# AC_dimmer_HLK.net
KiCad netlist of a schematic drawn in EAGLE
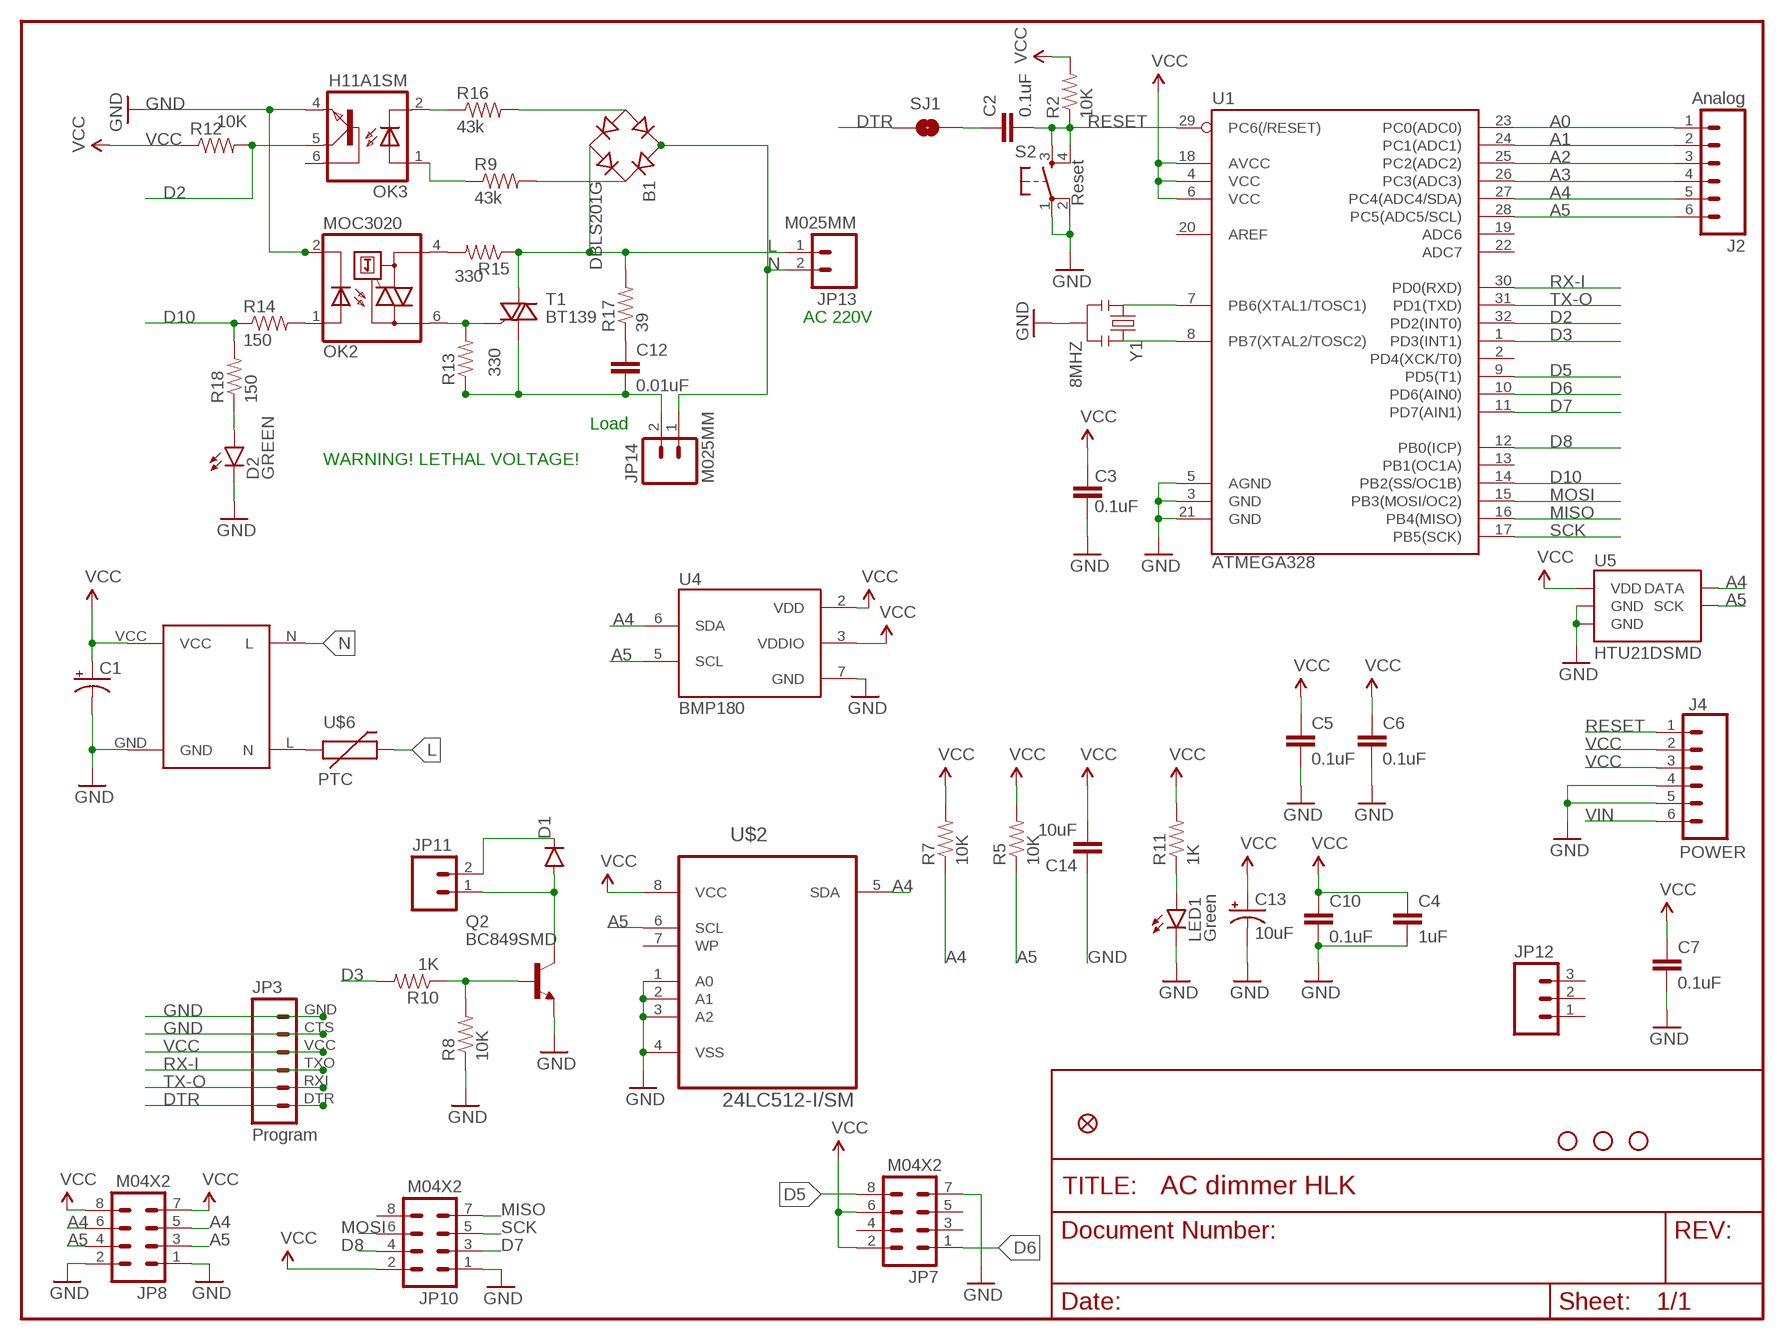
[diagram p0: schematic, sheet 1]

(export (version "E")
  (design (tool "Eeschema 10.0.6"))
  (components
    (comp (ref "B1")
      (value "DBLS201G")
      (footprint "eagle-import:DBS")
      (libsource (lib "eagle-import") (part "DB?GLS201"))
    )
    (comp (ref "C1")
      (value "CAP_POL3528-KIT")
      (footprint "eagle-import:EIA3528-KIT")
      (libsource (lib "eagle-import") (part "CAP_POL3528-KIT"))
    )
    (comp (ref "C2")
      (value "0.1uF")
      (footprint "eagle-import:0805")
      (libsource (lib "eagle-import") (part "CAP0805"))
    )
    (comp (ref "C3")
      (value "0.1uF")
      (footprint "eagle-import:0805")
      (libsource (lib "eagle-import") (part "CAP0805"))
    )
    (comp (ref "C4")
      (value "1uF")
      (footprint "eagle-import:0805")
      (libsource (lib "eagle-import") (part "CAP0805"))
    )
    (comp (ref "C5")
      (value "0.1uF")
      (footprint "eagle-import:0805")
      (libsource (lib "eagle-import") (part "CAP0805"))
    )
    (comp (ref "C6")
      (value "0.1uF")
      (footprint "eagle-import:0805")
      (libsource (lib "eagle-import") (part "CAP0805"))
    )
    (comp (ref "C7")
      (value "0.1uF")
      (footprint "eagle-import:0805")
      (libsource (lib "eagle-import") (part "CAP0805"))
    )
    (comp (ref "C10")
      (value "0.1uF")
      (footprint "eagle-import:0805")
      (libsource (lib "eagle-import") (part "CAP0805"))
    )
    (comp (ref "C12")
      (value "0.01uF")
      (footprint "eagle-import:C1206")
      (libsource (lib "eagle-import") (part "C-EUC1206"))
    )
    (comp (ref "C13")
      (value "10uF")
      (footprint "eagle-import:EIA3216")
      (libsource (lib "eagle-import") (part "CAP_POL1206"))
    )
    (comp (ref "C14")
      (value "10uF")
      (footprint "eagle-import:1206")
      (libsource (lib "eagle-import") (part "SparkFun-Capacitors_CAP1206"))
    )
    (comp (ref "D1")
      (value "DIODESOD")
      (footprint "eagle-import:SOD-323")
      (libsource (lib "eagle-import") (part "DIODESOD"))
    )
    (comp (ref "D2")
      (value "GREEN")
      (footprint "eagle-import:LED-0603")
      (libsource (lib "eagle-import") (part "LED0603"))
    )
    (comp (ref "J2")
      (value "Analog")
      (footprint "eagle-import:1X06")
      (libsource (lib "eagle-import") (part "M06SIP"))
    )
    (comp (ref "J4")
      (value "POWER")
      (footprint "eagle-import:1X06")
      (libsource (lib "eagle-import") (part "M06SIP"))
    )
    (comp (ref "JP2")
      (value "FIDUCIAL1X2.5")
      (footprint "eagle-import:FIDUCIAL-1X2.5")
      (libsource (lib "eagle-import") (part "FIDUCIAL1X2.5"))
    )
    (comp (ref "JP3")
      (value "Program")
      (footprint "eagle-import:1X06")
      (libsource (lib "eagle-import") (part "SparkFun-Connectors_M06SIP"))
    )
    (comp (ref "JP7")
      (value "M04X2")
      (footprint "eagle-import:2X4")
      (libsource (lib "eagle-import") (part "M04X2"))
    )
    (comp (ref "JP8")
      (value "M04X2")
      (footprint "eagle-import:2X4")
      (libsource (lib "eagle-import") (part "M04X2"))
    )
    (comp (ref "JP10")
      (value "M04X2")
      (footprint "eagle-import:2X4")
      (libsource (lib "eagle-import") (part "M04X2"))
    )
    (comp (ref "JP11")
      (value "M02PTH")
      (footprint "eagle-import:1X02")
      (libsource (lib "eagle-import") (part "M02PTH"))
    )
    (comp (ref "JP12")
      (value "M03PTH")
      (footprint "eagle-import:1X03")
      (libsource (lib "eagle-import") (part "M03PTH"))
    )
    (comp (ref "JP13")
      (value "M025MM")
      (footprint "eagle-import:SCREWTERMINAL-5MM-2")
      (libsource (lib "eagle-import") (part "M025MM"))
    )
    (comp (ref "JP14")
      (value "M025MM")
      (footprint "eagle-import:SCREWTERMINAL-5MM-2")
      (libsource (lib "eagle-import") (part "M025MM"))
    )
    (comp (ref "LED1")
      (value "Green")
      (footprint "eagle-import:LED-0603")
      (libsource (lib "eagle-import") (part "LED0603"))
    )
    (comp (ref "OK2")
      (value "MOC3020")
      (footprint "eagle-import:DIL6-SMD")
      (fields (field (name "MF") "FAIRCHILD SEMICONDUCTOR") (field (name "MPN") "MOC3031SM"))
      (libsource (lib "eagle-import") (part "MOC30S31"))
    )
    (comp (ref "OK3")
      (value "H11A1SM")
      (footprint "eagle-import:DIL6-SMD")
      (libsource (lib "eagle-import") (part "H11A?MS1"))
    )
    (comp (ref "Q2")
      (value "BC849SMD")
      (footprint "eagle-import:SOT23-BEC")
      (libsource (lib "eagle-import") (part "BC849SMD"))
    )
    (comp (ref "R2")
      (value "10K")
      (footprint "eagle-import:0805")
      (libsource (lib "eagle-import") (part "RESISTOR0805-RES"))
    )
    (comp (ref "R5")
      (value "10K")
      (footprint "eagle-import:0805")
      (libsource (lib "eagle-import") (part "RESISTOR0805-RES"))
    )
    (comp (ref "R7")
      (value "10K")
      (footprint "eagle-import:0805")
      (libsource (lib "eagle-import") (part "RESISTOR0805-RES"))
    )
    (comp (ref "R8")
      (value "10K")
      (footprint "eagle-import:0805")
      (libsource (lib "eagle-import") (part "RESISTOR0805-RES"))
    )
    (comp (ref "R9")
      (value "43k")
      (footprint "eagle-import:1206")
      (fields (field (name "K") "45K"))
      (libsource (lib "eagle-import") (part "SparkFun-Resistors_RESISTOR1206"))
    )
    (comp (ref "R10")
      (value "1K")
      (footprint "eagle-import:0805")
      (libsource (lib "eagle-import") (part "RESISTOR0805-RES"))
    )
    (comp (ref "R11")
      (value "1K")
      (footprint "eagle-import:0805")
      (libsource (lib "eagle-import") (part "RESISTOR0805-RES"))
    )
    (comp (ref "R12")
      (value "RESISTOR0805-RES")
      (footprint "eagle-import:0805")
      (fields (field (name "OHM") "10K"))
      (libsource (lib "eagle-import") (part "SparkFun-Resistors_RESISTOR0805-RES"))
    )
    (comp (ref "R13")
      (value "RESISTOR1206")
      (footprint "eagle-import:1206")
      (fields (field (name "OHM") "330"))
      (libsource (lib "eagle-import") (part "SparkFun-Resistors_RESISTOR1206"))
    )
    (comp (ref "R14")
      (value "150")
      (footprint "eagle-import:0805")
      (fields (field (name "OHM") "330"))
      (libsource (lib "eagle-import") (part "SparkFun-Resistors_RESISTOR0805-RES"))
    )
    (comp (ref "R15")
      (value "RESISTOR1206")
      (footprint "eagle-import:1206")
      (fields (field (name "OHM") "330"))
      (libsource (lib "eagle-import") (part "SparkFun-Resistors_RESISTOR1206"))
    )
    (comp (ref "R16")
      (value "43k")
      (footprint "eagle-import:1206")
      (fields (field (name "K") "45K"))
      (libsource (lib "eagle-import") (part "SparkFun-Resistors_RESISTOR1206"))
    )
    (comp (ref "R17")
      (value "39")
      (footprint "eagle-import:1206")
      (fields (field (name "K") "45K"))
      (libsource (lib "eagle-import") (part "SparkFun-Resistors_RESISTOR1206"))
    )
    (comp (ref "R18")
      (value "150")
      (footprint "eagle-import:0805")
      (fields (field (name "OHM") "330"))
      (libsource (lib "eagle-import") (part "SparkFun-Resistors_RESISTOR0805-RES"))
    )
    (comp (ref "S2")
      (value "Reset")
      (footprint "eagle-import:TACTILE_SWITCH_SMD")
      (libsource (lib "eagle-import") (part "TAC_SWITCHSMD"))
    )
    (comp (ref "SJ1")
      (value "SOLDERJUMPERNC2")
      (footprint "eagle-import:SJ_2S-NOTRACE")
      (libsource (lib "eagle-import") (part "SOLDERJUMPERNC2"))
    )
    (comp (ref "T1")
      (value "BT139")
      (footprint "eagle-import:TO220AB")
      (libsource (lib "eagle-import") (part "BT136"))
    )
    (comp (ref "U$2")
      (value "24LC512-I/SM")
      (footprint "eagle-import:SOIC127P794X203-8N")
      (libsource (lib "eagle-import") (part "24LC512-I/SM"))
    )
    (comp (ref "U$3")
      (value "STAND-OFFTIGHT")
      (footprint "eagle-import:STAND-OFF-TIGHT")
      (libsource (lib "eagle-import") (part "STAND-OFFTIGHT"))
    )
    (comp (ref "U$5")
      (value "AC-DCHLK01")
      (footprint "eagle-import:HLK-PM01")
      (libsource (lib "eagle-import") (part "AC-DCHLK01"))
    )
    (comp (ref "U$6")
      (value "PTC")
      (footprint "eagle-import:MC331XX")
      (libsource (lib "eagle-import") (part "PTC"))
    )
    (comp (ref "U$9")
      (value "STAND-OFFTIGHT")
      (footprint "eagle-import:STAND-OFF-TIGHT")
      (libsource (lib "eagle-import") (part "STAND-OFFTIGHT"))
    )
    (comp (ref "U$10")
      (value "STAND-OFFTIGHT")
      (footprint "eagle-import:STAND-OFF-TIGHT")
      (libsource (lib "eagle-import") (part "STAND-OFFTIGHT"))
    )
    (comp (ref "U1")
      (value "ATMEGA328")
      (footprint "eagle-import:TQFP32-08")
      (libsource (lib "eagle-import") (part "ATMEGA168"))
    )
    (comp (ref "U4")
      (value "BMP180")
      (footprint "eagle-import:BMP180")
      (libsource (lib "eagle-import") (part "BMP180"))
    )
    (comp (ref "U5")
      (value "HTU21DSMD")
      (footprint "eagle-import:HTU21D")
      (libsource (lib "eagle-import") (part "HTU21DSMD"))
    )
    (comp (ref "Y1")
      (value "8MHZ")
      (footprint "eagle-import:RESONATOR-SMD")
      (libsource (lib "eagle-import") (part "RESONATOR8MHZ"))
    )
  )
  (nets
    (net (code "1") (name "/A0") (class "Default")
      (node (ref "J2") (pin "1") (pinfunction "1_1") (pintype "passive"))
      (node (ref "U1") (pin "23") (pinfunction "PC0(ADC0)_23") (pintype "bidirectional"))
    )
    (net (code "2") (name "/A1") (class "Default")
      (node (ref "J2") (pin "2") (pinfunction "2_2") (pintype "passive"))
      (node (ref "U1") (pin "24") (pinfunction "PC1(ADC1)_24") (pintype "bidirectional"))
    )
    (net (code "3") (name "/A2") (class "Default")
      (node (ref "J2") (pin "3") (pinfunction "3_3") (pintype "passive"))
      (node (ref "U1") (pin "25") (pinfunction "PC2(ADC2)_25") (pintype "bidirectional"))
    )
    (net (code "4") (name "/A3") (class "Default")
      (node (ref "J2") (pin "4") (pinfunction "4_4") (pintype "passive"))
      (node (ref "U1") (pin "26") (pinfunction "PC3(ADC3)_26") (pintype "bidirectional"))
    )
    (net (code "5") (name "/A4") (class "Default")
      (node (ref "J2") (pin "5") (pinfunction "5_5") (pintype "passive"))
      (node (ref "JP8") (pin "5") (pinfunction "5_5") (pintype "passive"))
      (node (ref "JP8") (pin "6") (pinfunction "6_6") (pintype "passive"))
      (node (ref "R7") (pin "1") (pinfunction "1_1") (pintype "passive"))
      (node (ref "U$2") (pin "5") (pinfunction "SDA_5") (pintype "bidirectional"))
      (node (ref "U1") (pin "27") (pinfunction "PC4(ADC4/SDA)_27") (pintype "bidirectional"))
      (node (ref "U4") (pin "6") (pinfunction "SDA_6") (pintype "bidirectional"))
      (node (ref "U5") (pin "DATA") (pinfunction "DATA_DATA") (pintype "bidirectional"))
    )
    (net (code "6") (name "/A5") (class "Default")
      (node (ref "J2") (pin "6") (pinfunction "6_6") (pintype "passive"))
      (node (ref "JP8") (pin "3") (pinfunction "3_3") (pintype "passive"))
      (node (ref "JP8") (pin "4") (pinfunction "4_4") (pintype "passive"))
      (node (ref "R5") (pin "1") (pinfunction "1_1") (pintype "passive"))
      (node (ref "U$2") (pin "6") (pinfunction "SCL_6") (pintype "input"))
      (node (ref "U1") (pin "28") (pinfunction "PC5(ADC5/SCL)_28") (pintype "bidirectional"))
      (node (ref "U4") (pin "5") (pinfunction "SCL_5") (pintype "input"))
      (node (ref "U5") (pin "SCK") (pinfunction "SCK_SCK") (pintype "input"))
    )
    (net (code "7") (name "/D2") (class "Default")
      (node (ref "OK3") (pin "5") (pinfunction "COL_5") (pintype "passive"))
      (node (ref "R12") (pin "2") (pinfunction "2_2") (pintype "passive"))
      (node (ref "U1") (pin "32") (pinfunction "PD2(INT0)_32") (pintype "bidirectional"))
    )
    (net (code "8") (name "/D3") (class "Default")
      (node (ref "R10") (pin "2") (pinfunction "2_2") (pintype "passive"))
      (node (ref "U1") (pin "1") (pinfunction "PD3(INT1)_1") (pintype "bidirectional"))
    )
    (net (code "9") (name "/D7") (class "Default")
      (node (ref "JP10") (pin "3") (pinfunction "3_3") (pintype "passive"))
      (node (ref "U1") (pin "11") (pinfunction "PD7(AIN1)_11") (pintype "bidirectional"))
    )
    (net (code "10") (name "/D8") (class "Default")
      (node (ref "JP10") (pin "4") (pinfunction "4_4") (pintype "passive"))
      (node (ref "U1") (pin "12") (pinfunction "PB0(ICP)_12") (pintype "bidirectional"))
    )
    (net (code "11") (name "/D10") (class "Default")
      (node (ref "R14") (pin "1") (pinfunction "1_1") (pintype "passive"))
      (node (ref "R18") (pin "2") (pinfunction "2_2") (pintype "passive"))
      (node (ref "U1") (pin "14") (pinfunction "PB2(SS/OC1B)_14") (pintype "bidirectional"))
    )
    (net (code "12") (name "/DTR") (class "Default")
      (node (ref "JP3") (pin "DTR") (pinfunction "1_DTR") (pintype "passive"))
      (node (ref "SJ1") (pin "1") (pinfunction "1_1") (pintype "passive"))
    )
    (net (code "13") (name "/MISO") (class "Default")
      (node (ref "JP10") (pin "7") (pinfunction "7_7") (pintype "passive"))
      (node (ref "U1") (pin "16") (pinfunction "PB4(MISO)_16") (pintype "bidirectional"))
    )
    (net (code "14") (name "/MOSI") (class "Default")
      (node (ref "JP10") (pin "6") (pinfunction "6_6") (pintype "passive"))
      (node (ref "U1") (pin "15") (pinfunction "PB3(MOSI/OC2)_15") (pintype "bidirectional"))
    )
    (net (code "15") (name "/RESET") (class "Default")
      (node (ref "C2") (pin "2") (pinfunction "2_2") (pintype "passive"))
      (node (ref "J4") (pin "1") (pinfunction "1_1") (pintype "passive"))
      (node (ref "R2") (pin "1") (pinfunction "1_1") (pintype "passive"))
      (node (ref "S2") (pin "3") (pinfunction "3_3") (pintype "passive"))
      (node (ref "S2") (pin "4") (pinfunction "4_4") (pintype "passive"))
      (node (ref "U1") (pin "29") (pinfunction "PC6(/RESET)_29") (pintype "bidirectional"))
    )
    (net (code "16") (name "/RX-I") (class "Default")
      (node (ref "JP3") (pin "TXO") (pinfunction "3_TXO") (pintype "passive"))
      (node (ref "U1") (pin "30") (pinfunction "PD0(RXD)_30") (pintype "bidirectional"))
    )
    (net (code "17") (name "/SCK") (class "Default")
      (node (ref "JP10") (pin "5") (pinfunction "5_5") (pintype "passive"))
      (node (ref "U1") (pin "17") (pinfunction "PB5(SCK)_17") (pintype "bidirectional"))
    )
    (net (code "18") (name "/TX-O") (class "Default")
      (node (ref "JP3") (pin "RXI") (pinfunction "2_RXI") (pintype "passive"))
      (node (ref "U1") (pin "31") (pinfunction "PD1(TXD)_31") (pintype "bidirectional"))
    )
    (net (code "19") (name "/VIN") (class "Default")
      (node (ref "J4") (pin "6") (pinfunction "6_6") (pintype "passive"))
    )
    (net (code "20") (name "D5") (class "Default")
      (node (ref "JP7") (pin "8") (pinfunction "8_8") (pintype "passive"))
      (node (ref "U1") (pin "9") (pinfunction "PD5(T1)_9") (pintype "bidirectional"))
    )
    (net (code "21") (name "D6") (class "Default")
      (node (ref "JP7") (pin "1") (pinfunction "1_1") (pintype "passive"))
      (node (ref "U1") (pin "10") (pinfunction "PD6(AIN0)_10") (pintype "bidirectional"))
    )
    (net (code "22") (name "GND") (class "Default")
      (node (ref "C1") (pin "C") (pinfunction "-_C") (pintype "passive"))
      (node (ref "C10") (pin "2") (pinfunction "2_2") (pintype "passive"))
      (node (ref "C13") (pin "C") (pinfunction "-_C") (pintype "passive"))
      (node (ref "C14") (pin "1") (pinfunction "1_1") (pintype "passive"))
      (node (ref "C3") (pin "1") (pinfunction "1_1") (pintype "passive"))
      (node (ref "C4") (pin "2") (pinfunction "2_2") (pintype "passive"))
      (node (ref "C5") (pin "2") (pinfunction "2_2") (pintype "passive"))
      (node (ref "C6") (pin "2") (pinfunction "2_2") (pintype "passive"))
      (node (ref "C7") (pin "2") (pinfunction "2_2") (pintype "passive"))
      (node (ref "D2") (pin "C") (pinfunction "C_C") (pintype "passive"))
      (node (ref "J4") (pin "4") (pinfunction "4_4") (pintype "passive"))
      (node (ref "J4") (pin "5") (pinfunction "5_5") (pintype "passive"))
      (node (ref "JP10") (pin "1") (pinfunction "1_1") (pintype "passive"))
      (node (ref "JP3") (pin "CTS") (pinfunction "5_CTS") (pintype "passive"))
      (node (ref "JP3") (pin "GND") (pinfunction "6_GND") (pintype "passive"))
      (node (ref "JP7") (pin "7") (pinfunction "7_7") (pintype "passive"))
      (node (ref "JP8") (pin "1") (pinfunction "1_1") (pintype "passive"))
      (node (ref "JP8") (pin "2") (pinfunction "2_2") (pintype "passive"))
      (node (ref "LED1") (pin "C") (pinfunction "C_C") (pintype "passive"))
      (node (ref "OK2") (pin "2") (pinfunction "C_2") (pintype "passive"))
      (node (ref "OK3") (pin "4") (pinfunction "EMI_4") (pintype "passive"))
      (node (ref "Q2") (pin "E") (pinfunction "E_E") (pintype "passive"))
      (node (ref "R8") (pin "1") (pinfunction "1_1") (pintype "passive"))
      (node (ref "S2") (pin "1") (pinfunction "1_1") (pintype "passive"))
      (node (ref "S2") (pin "2") (pinfunction "2_2") (pintype "passive"))
      (node (ref "U$2") (pin "1") (pinfunction "A0_1") (pintype "input"))
      (node (ref "U$2") (pin "2") (pinfunction "A1_2") (pintype "input"))
      (node (ref "U$2") (pin "3") (pinfunction "A2_3") (pintype "input"))
      (node (ref "U$2") (pin "4") (pinfunction "VSS_4") (pintype "passive"))
      (node (ref "U$5") (pin "GND") (pinfunction "GND_GND") (pintype "bidirectional"))
      (node (ref "U1") (pin "21") (pinfunction "GND_21") (pintype "bidirectional"))
      (node (ref "U1") (pin "3") (pinfunction "GND_3") (pintype "bidirectional"))
      (node (ref "U1") (pin "5") (pinfunction "AGND_5") (pintype "bidirectional"))
      (node (ref "U4") (pin "7") (pinfunction "GND_7") (pintype "power_in"))
      (node (ref "U5") (pin "7") (pinfunction "GND_7") (pintype "power_in"))
      (node (ref "U5") (pin "GND") (pinfunction "GND_GND") (pintype "power_in"))
      (node (ref "Y1") (pin "2") (pinfunction "2_2") (pintype "passive"))
    )
    (net (code "23") (name "L") (class "Default")
      (node (ref "B1") (pin "AC2") (pinfunction "AC2_AC2") (pintype "passive"))
      (node (ref "JP13") (pin "1") (pinfunction "1_1") (pintype "passive"))
      (node (ref "R15") (pin "1") (pinfunction "1_1") (pintype "passive"))
      (node (ref "R17") (pin "2") (pinfunction "2_2") (pintype "passive"))
      (node (ref "T1") (pin "2") (pinfunction "A2_2") (pintype "passive"))
      (node (ref "U$6") (pin "P$2") (pinfunction "2_P$2") (pintype "bidirectional"))
    )
    (net (code "24") (name "N") (class "Default")
      (node (ref "B1") (pin "AC1") (pinfunction "AC1_AC1") (pintype "passive"))
      (node (ref "JP13") (pin "2") (pinfunction "2_2") (pintype "passive"))
      (node (ref "JP14") (pin "1") (pinfunction "1_1") (pintype "passive"))
      (node (ref "U$5") (pin "N") (pinfunction "L_N") (pintype "bidirectional"))
    )
    (net (code "25") (name "Net-(B1-Pad+)") (class "Default")
      (node (ref "B1") (pin "+") (pinfunction "+_+") (pintype "passive"))
      (node (ref "R9") (pin "2") (pinfunction "2_2") (pintype "passive"))
    )
    (net (code "26") (name "Net-(B1-Pad-)") (class "Default")
      (node (ref "B1") (pin "-") (pinfunction "-_-") (pintype "passive"))
      (node (ref "R16") (pin "2") (pinfunction "2_2") (pintype "passive"))
    )
    (net (code "27") (name "Net-(C2-Pad1)") (class "Default")
      (node (ref "C2") (pin "1") (pinfunction "1_1") (pintype "passive"))
      (node (ref "SJ1") (pin "2") (pinfunction "2_2") (pintype "passive"))
    )
    (net (code "28") (name "Net-(C12-Pad1)") (class "Default")
      (node (ref "C12") (pin "1") (pinfunction "1_1") (pintype "passive"))
      (node (ref "R17") (pin "1") (pinfunction "1_1") (pintype "passive"))
    )
    (net (code "29") (name "Net-(D1-PadA)") (class "Default")
      (node (ref "D1") (pin "A") (pinfunction "A_A") (pintype "passive"))
      (node (ref "JP11") (pin "1") (pinfunction "1_1") (pintype "passive"))
      (node (ref "Q2") (pin "C") (pinfunction "C_C") (pintype "passive"))
    )
    (net (code "30") (name "Net-(D1-PadC)") (class "Default")
      (node (ref "D1") (pin "C") (pinfunction "C_C") (pintype "passive"))
      (node (ref "JP11") (pin "2") (pinfunction "2_2") (pintype "passive"))
    )
    (net (code "31") (name "Net-(D2-PadA)") (class "Default")
      (node (ref "D2") (pin "A") (pinfunction "A_A") (pintype "passive"))
      (node (ref "R18") (pin "1") (pinfunction "1_1") (pintype "passive"))
    )
    (net (code "32") (name "Net-(LED1-PadA)") (class "Default")
      (node (ref "LED1") (pin "A") (pinfunction "A_A") (pintype "passive"))
      (node (ref "R11") (pin "1") (pinfunction "1_1") (pintype "passive"))
    )
    (net (code "33") (name "Net-(OK2-A)") (class "Default")
      (node (ref "OK2") (pin "1") (pinfunction "A_1") (pintype "passive"))
      (node (ref "R14") (pin "2") (pinfunction "2_2") (pintype "passive"))
    )
    (net (code "34") (name "Net-(OK2-A1)") (class "Default")
      (node (ref "OK2") (pin "4") (pinfunction "A1_4") (pintype "passive"))
      (node (ref "R15") (pin "2") (pinfunction "2_2") (pintype "passive"))
    )
    (net (code "35") (name "Net-(OK2-A2)") (class "Default")
      (node (ref "OK2") (pin "6") (pinfunction "A2_6") (pintype "passive"))
      (node (ref "R13") (pin "2") (pinfunction "2_2") (pintype "passive"))
      (node (ref "T1") (pin "3") (pinfunction "G_3") (pintype "passive"))
    )
    (net (code "36") (name "Net-(OK3-A)") (class "Default")
      (node (ref "OK3") (pin "1") (pinfunction "A_1") (pintype "passive"))
      (node (ref "R9") (pin "1") (pinfunction "1_1") (pintype "passive"))
    )
    (net (code "37") (name "Net-(OK3-C)") (class "Default")
      (node (ref "OK3") (pin "2") (pinfunction "C_2") (pintype "passive"))
      (node (ref "R16") (pin "1") (pinfunction "1_1") (pintype "passive"))
    )
    (net (code "38") (name "Net-(Q2-PadB)") (class "Default")
      (node (ref "Q2") (pin "B") (pinfunction "B_B") (pintype "passive"))
      (node (ref "R10") (pin "1") (pinfunction "1_1") (pintype "passive"))
      (node (ref "R8") (pin "2") (pinfunction "2_2") (pintype "passive"))
    )
    (net (code "39") (name "Net-(T1-A1)") (class "Default")
      (node (ref "C12") (pin "2") (pinfunction "2_2") (pintype "passive"))
      (node (ref "JP14") (pin "2") (pinfunction "2_2") (pintype "passive"))
      (node (ref "R13") (pin "1") (pinfunction "1_1") (pintype "passive"))
      (node (ref "T1") (pin "1") (pinfunction "A1_1") (pintype "passive"))
    )
    (net (code "40") (name "Net-(U$5-N)") (class "Default")
      (node (ref "U$5") (pin "L") (pinfunction "N_L") (pintype "bidirectional"))
      (node (ref "U$6") (pin "P$1") (pinfunction "1_P$1") (pintype "bidirectional"))
    )
    (net (code "41") (name "Net-(U1-PB6(XTAL1{slash}TOSC1))") (class "Default")
      (node (ref "U1") (pin "7") (pinfunction "PB6(XTAL1/TOSC1)_7") (pintype "bidirectional"))
      (node (ref "Y1") (pin "1") (pinfunction "1_1") (pintype "passive"))
    )
    (net (code "42") (name "Net-(U1-PB7(XTAL2{slash}TOSC2))") (class "Default")
      (node (ref "U1") (pin "8") (pinfunction "PB7(XTAL2/TOSC2)_8") (pintype "bidirectional"))
      (node (ref "Y1") (pin "3") (pinfunction "3_3") (pintype "passive"))
    )
    (net (code "43") (name "VCC") (class "Default")
      (node (ref "C1") (pin "A") (pinfunction "+_A") (pintype "passive"))
      (node (ref "C10") (pin "1") (pinfunction "1_1") (pintype "passive"))
      (node (ref "C13") (pin "A") (pinfunction "+_A") (pintype "passive"))
      (node (ref "C14") (pin "2") (pinfunction "2_2") (pintype "passive"))
      (node (ref "C3") (pin "2") (pinfunction "2_2") (pintype "passive"))
      (node (ref "C4") (pin "1") (pinfunction "1_1") (pintype "passive"))
      (node (ref "C5") (pin "1") (pinfunction "1_1") (pintype "passive"))
      (node (ref "C6") (pin "1") (pinfunction "1_1") (pintype "passive"))
      (node (ref "C7") (pin "1") (pinfunction "1_1") (pintype "passive"))
      (node (ref "J4") (pin "2") (pinfunction "2_2") (pintype "passive"))
      (node (ref "J4") (pin "3") (pinfunction "3_3") (pintype "passive"))
      (node (ref "JP10") (pin "2") (pinfunction "2_2") (pintype "passive"))
      (node (ref "JP3") (pin "VCC") (pinfunction "4_VCC") (pintype "passive"))
      (node (ref "JP7") (pin "2") (pinfunction "2_2") (pintype "passive"))
      (node (ref "JP7") (pin "6") (pinfunction "6_6") (pintype "passive"))
      (node (ref "JP8") (pin "7") (pinfunction "7_7") (pintype "passive"))
      (node (ref "JP8") (pin "8") (pinfunction "8_8") (pintype "passive"))
      (node (ref "R11") (pin "2") (pinfunction "2_2") (pintype "passive"))
      (node (ref "R12") (pin "1") (pinfunction "1_1") (pintype "passive"))
      (node (ref "R2") (pin "2") (pinfunction "2_2") (pintype "passive"))
      (node (ref "R5") (pin "2") (pinfunction "2_2") (pintype "passive"))
      (node (ref "R7") (pin "2") (pinfunction "2_2") (pintype "passive"))
      (node (ref "U$2") (pin "8") (pinfunction "VCC_8") (pintype "power_in"))
      (node (ref "U$5") (pin "VCC") (pinfunction "VCC_VCC") (pintype "bidirectional"))
      (node (ref "U1") (pin "18") (pinfunction "AVCC_18") (pintype "bidirectional"))
      (node (ref "U1") (pin "4") (pinfunction "VCC_4") (pintype "bidirectional"))
      (node (ref "U1") (pin "6") (pinfunction "VCC_6") (pintype "bidirectional"))
      (node (ref "U4") (pin "2") (pinfunction "VDD_2") (pintype "power_in"))
      (node (ref "U4") (pin "3") (pinfunction "VDDIO_3") (pintype "power_in"))
      (node (ref "U5") (pin "VDD") (pinfunction "VDD_VDD") (pintype "power_in"))
    )
    (net (code "44") (name "unconnected-(JP7-Pad3)") (class "Default")
      (node (ref "JP7") (pin "3") (pinfunction "3_3") (pintype "passive"))
    )
    (net (code "45") (name "unconnected-(JP7-Pad4)") (class "Default")
      (node (ref "JP7") (pin "4") (pinfunction "4_4") (pintype "passive"))
    )
    (net (code "46") (name "unconnected-(JP7-Pad5)") (class "Default")
      (node (ref "JP7") (pin "5") (pinfunction "5_5") (pintype "passive"))
    )
    (net (code "47") (name "unconnected-(JP10-Pad8)") (class "Default")
      (node (ref "JP10") (pin "8") (pinfunction "8_8") (pintype "passive"))
    )
    (net (code "48") (name "unconnected-(JP12-Pad1)") (class "Default")
      (node (ref "JP12") (pin "1") (pinfunction "1_1") (pintype "passive"))
    )
    (net (code "49") (name "unconnected-(JP12-Pad2)") (class "Default")
      (node (ref "JP12") (pin "2") (pinfunction "2_2") (pintype "passive"))
    )
    (net (code "50") (name "unconnected-(JP12-Pad3)") (class "Default")
      (node (ref "JP12") (pin "3") (pinfunction "3_3") (pintype "passive"))
    )
    (net (code "51") (name "unconnected-(OK3-BAS-Pad6)") (class "Default")
      (node (ref "OK3") (pin "6") (pinfunction "BAS_6") (pintype "passive"))
    )
    (net (code "52") (name "unconnected-(U$2-WP-Pad7)") (class "Default")
      (node (ref "U$2") (pin "7") (pinfunction "WP_7") (pintype "input"))
    )
    (net (code "53") (name "unconnected-(U1-ADC6-Pad19)") (class "Default")
      (node (ref "U1") (pin "19") (pinfunction "ADC6_19") (pintype "bidirectional"))
    )
    (net (code "54") (name "unconnected-(U1-ADC7-Pad22)") (class "Default")
      (node (ref "U1") (pin "22") (pinfunction "ADC7_22") (pintype "bidirectional"))
    )
    (net (code "55") (name "unconnected-(U1-AREF-Pad20)") (class "Default")
      (node (ref "U1") (pin "20") (pinfunction "AREF_20") (pintype "bidirectional"))
    )
    (net (code "56") (name "unconnected-(U1-PB1(OC1A)-Pad13)") (class "Default")
      (node (ref "U1") (pin "13") (pinfunction "PB1(OC1A)_13") (pintype "bidirectional"))
    )
    (net (code "57") (name "unconnected-(U1-PD4(XCK{slash}T0)-Pad2)") (class "Default")
      (node (ref "U1") (pin "2") (pinfunction "PD4(XCK/T0)_2") (pintype "bidirectional"))
    )
  )
)
